# REGULATOR.net
KiCad netlist of a schematic drawn in Altium Designer
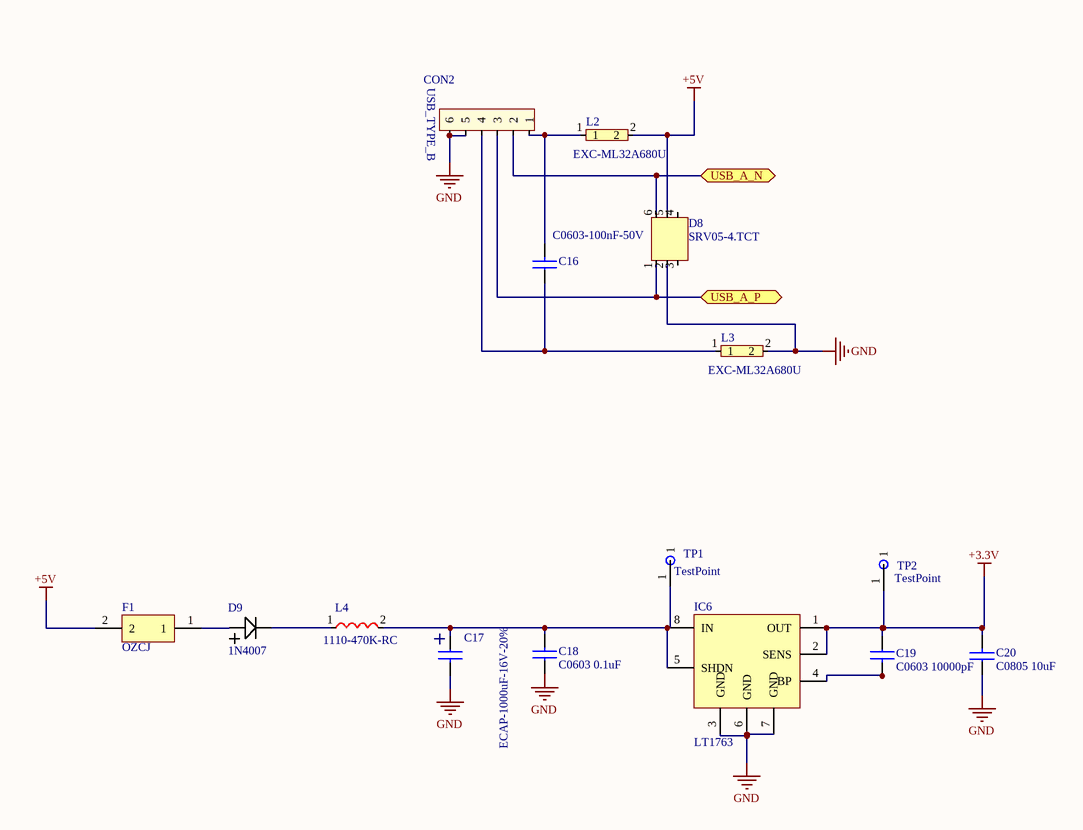
[diagram p0: REGULATOR.SchDoc]

(export (version "E")
  (design (tool "Eeschema 10.0.6"))
  (components
    (comp (ref "C16")
      (value "C0603-100nF-50V")
      (footprint "C0603")
      (description "CL10B104KB8NNNC")
      (libsource (lib "COOP4403_BerkantAY") (part "C0603-100nF-50V"))
    )
    (comp (ref "C17")
      (value "ECAP-1000uF-16V-20%")
      (footprint "CAP_SMT")
      (description "CAP ALUM 1000pF 20% 16V / UCL1C102MNL1GS")
      (libsource (lib "COOP4403_BerkantAY") (part "ECAP-1000uF-16V-20%"))
    )
    (comp (ref "C18")
      (value "C0603 0.1uF")
      (footprint "C0603")
      (description "CAP CER 0.1uF 16V X7R 0603 / CL10B104K08NNNC")
      (libsource (lib "COOP4403_BerkantAY") (part "C0603 0.1uF"))
    )
    (comp (ref "C19")
      (value "C0603 10000pF")
      (footprint "C0603")
      (description "CAP CER 10000pF 25V 10% X7R 0603 / CL10B103KA8NNNC")
      (libsource (lib "COOP4403_BerkantAY") (part "C0603 10000pF"))
    )
    (comp (ref "C20")
      (value "C0805 10uF")
      (footprint "C0805")
      (description "CAP CER 10uF 6.3V X7R 0805 / C0805C106K9RACTU")
      (libsource (lib "COOP4403_BerkantAY") (part "C0805 10uF"))
    )
    (comp (ref "CON2")
      (value "~")
      (footprint "CON_670688000")
      (description "CONN USB RT ANG RECPT TYPE B BLK")
      (libsource (lib "COOP4403_BerkantAY") (part "670688000"))
    )
    (comp (ref "D8")
      (value "SRV05-4.TCT")
      (footprint "SOT23")
      (description "TVS DIODE 5V 17.5V DIODE SOT23-6")
      (libsource (lib "COOP4403_BerkantAY") (part "SRV05-4.TCT"))
    )
    (comp (ref "D9")
      (value "1N4007")
      (footprint "1N4007")
      (description "ONSEMI 1N4007")
      (libsource (lib "COOP4403_BerkantAY") (part "1N4007"))
    )
    (comp (ref "F1") (value "OZCJ") (footprint "OZCJ") (libsource (lib "COOP4403_BerkantAY") (part "OZCJ")))
    (comp (ref "IC6")
      (value "LT1763")
      (footprint "SOIC127P600X170-8N")
      (libsource (lib "COOP4403_BerkantAY") (part "LT1763"))
    )
    (comp (ref "L2")
      (value "EXC-ML32A680U")
      (footprint "L1608")
      (description "FERRITE BEAD 68 OHM 1206")
      (libsource (lib "COOP4403_BerkantAY") (part "EXC-ML32A680U"))
    )
    (comp (ref "L3")
      (value "EXC-ML32A680U")
      (footprint "L1608")
      (description "FERRITE BEAD 68 OHM 1206")
      (libsource (lib "COOP4403_BerkantAY") (part "EXC-ML32A680U"))
    )
    (comp (ref "L4")
      (value "1110-470K-RC")
      (footprint "1110 Coil")
      (description "FIXED IND 47UH 2.8A 62MOHM TH")
      (libsource (lib "COOP4403_BerkantAY") (part "1110-470K-RC"))
    )
    (comp (ref "TP1")
      (value "TestPoint")
      (footprint "TestPoint")
      (libsource (lib "COOP4403_BerkantAY") (part "TestPoint"))
    )
    (comp (ref "TP2")
      (value "TestPoint")
      (footprint "TestPoint")
      (libsource (lib "COOP4403_BerkantAY") (part "TestPoint"))
    )
  )
  (nets
    (net (code "1") (name "+3.3V") (class "Default")
      (node (ref "C19") (pin "1") (pinfunction "1_1") (pintype "passive"))
      (node (ref "C20") (pin "2") (pinfunction "2_2") (pintype "passive"))
      (node (ref "IC6") (pin "1") (pinfunction "OUT_1") (pintype "passive"))
      (node (ref "IC6") (pin "2") (pinfunction "SENS_2") (pintype "passive"))
      (node (ref "TP2") (pin "1") (pinfunction "1_1") (pintype "passive"))
    )
    (net (code "2") (name "+5V") (class "Default")
      (node (ref "D8") (pin "5") (pinfunction "5_5") (pintype "passive"))
      (node (ref "F1") (pin "2") (pinfunction "2_2") (pintype "passive"))
      (node (ref "L2") (pin "2") (pinfunction "2_2") (pintype "passive"))
    )
    (net (code "3") (name "/USB_A_N") (class "Default")
      (node (ref "CON2") (pin "2") (pinfunction "2_2") (pintype "passive"))
      (node (ref "D8") (pin "6") (pinfunction "6_6") (pintype "passive"))
    )
    (net (code "4") (name "/USB_A_P") (class "Default")
      (node (ref "CON2") (pin "3") (pinfunction "3_3") (pintype "passive"))
      (node (ref "D8") (pin "1") (pinfunction "1_1") (pintype "passive"))
    )
    (net (code "5") (name "GND") (class "Default")
      (node (ref "C17") (pin "2") (pinfunction "2_2") (pintype "passive"))
      (node (ref "C18") (pin "1") (pinfunction "1_1") (pintype "passive"))
      (node (ref "C20") (pin "1") (pinfunction "1_1") (pintype "passive"))
      (node (ref "CON2") (pin "5") (pinfunction "5_5") (pintype "passive"))
      (node (ref "CON2") (pin "6") (pinfunction "6_6") (pintype "passive"))
      (node (ref "D8") (pin "2") (pinfunction "2_2") (pintype "passive"))
      (node (ref "IC6") (pin "3") (pinfunction "GND_3") (pintype "passive"))
      (node (ref "IC6") (pin "6") (pinfunction "GND_6") (pintype "passive"))
      (node (ref "IC6") (pin "7") (pinfunction "GND_7") (pintype "passive"))
      (node (ref "L3") (pin "2") (pinfunction "2_2") (pintype "passive"))
    )
    (net (code "6") (name "Net-(C16-Pad1)") (class "Default")
      (node (ref "C16") (pin "1") (pinfunction "1_1") (pintype "passive"))
      (node (ref "CON2") (pin "4") (pinfunction "4_4") (pintype "passive"))
      (node (ref "L3") (pin "1") (pinfunction "1_1") (pintype "passive"))
    )
    (net (code "7") (name "Net-(C16-Pad2)") (class "Default")
      (node (ref "C16") (pin "2") (pinfunction "2_2") (pintype "passive"))
      (node (ref "CON2") (pin "1") (pinfunction "1_1") (pintype "passive"))
      (node (ref "L2") (pin "1") (pinfunction "1_1") (pintype "passive"))
    )
    (net (code "8") (name "Net-(D9-Pad1)") (class "Default")
      (node (ref "D9") (pin "1") (pinfunction "1_1") (pintype "passive"))
      (node (ref "F1") (pin "1") (pinfunction "1_1") (pintype "passive"))
    )
    (net (code "9") (name "Net-(D9-Pad2)") (class "Default")
      (node (ref "D9") (pin "2") (pintype "passive"))
      (node (ref "L4") (pin "1") (pinfunction "1_1") (pintype "passive"))
    )
    (net (code "10") (name "Net-(IC6-BP)") (class "Default")
      (node (ref "C19") (pin "2") (pinfunction "2_2") (pintype "passive"))
      (node (ref "IC6") (pin "4") (pinfunction "BP_4") (pintype "passive"))
    )
    (net (code "11") (name "Net-(IC6-IN)") (class "Default")
      (node (ref "C17") (pin "1") (pinfunction "1_1") (pintype "passive"))
      (node (ref "C18") (pin "2") (pinfunction "2_2") (pintype "passive"))
      (node (ref "IC6") (pin "5") (pinfunction "SHDN_5") (pintype "passive"))
      (node (ref "IC6") (pin "8") (pinfunction "IN_8") (pintype "passive"))
      (node (ref "L4") (pin "2") (pinfunction "2_2") (pintype "passive"))
      (node (ref "TP1") (pin "1") (pinfunction "1_1") (pintype "passive"))
    )
    (net (code "12") (name "unconnected-(D8-Pad3)") (class "Default")
      (node (ref "D8") (pin "3") (pinfunction "3_3") (pintype "passive"))
    )
    (net (code "13") (name "unconnected-(D8-Pad4)") (class "Default")
      (node (ref "D8") (pin "4") (pinfunction "4_4") (pintype "passive"))
    )
  )
)
